# RefOsc10MHz_1V1.net
KiCad netlist of a schematic drawn in EAGLE
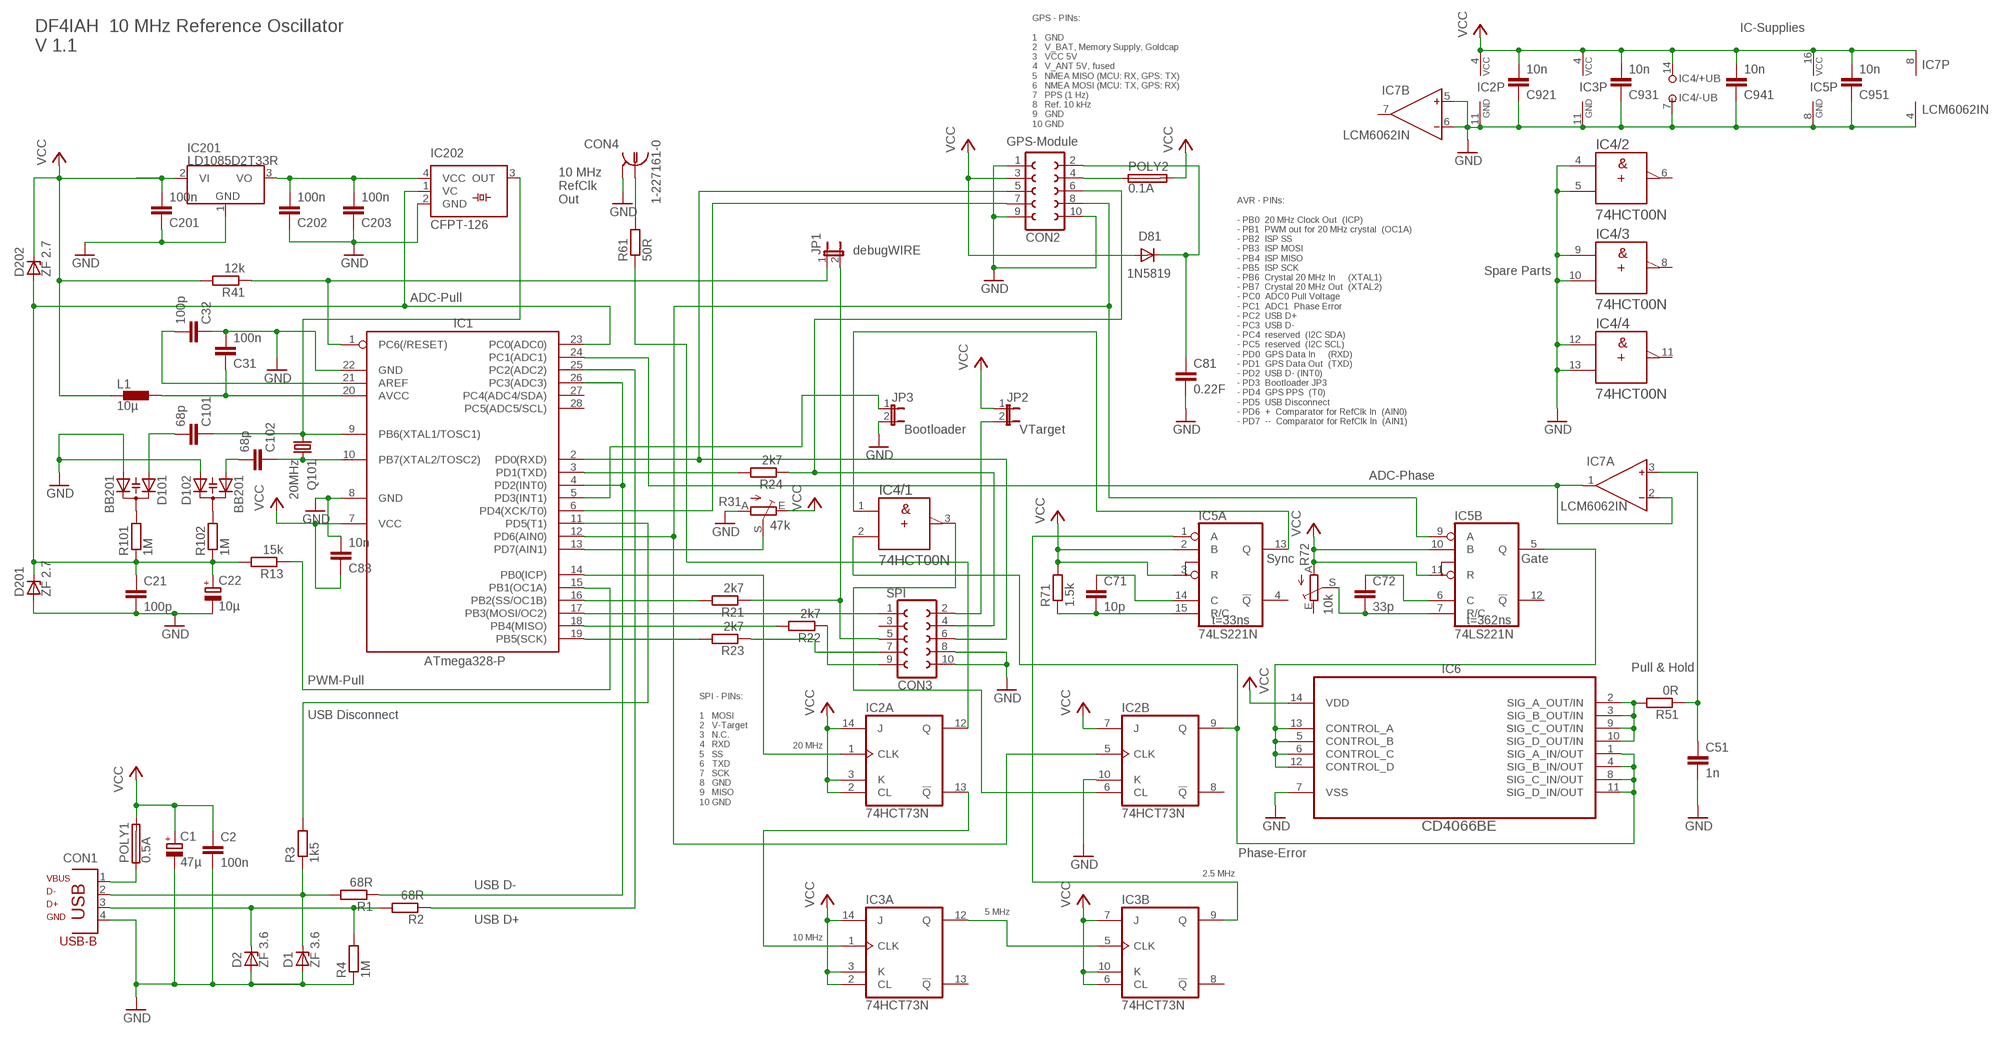
[diagram p0: schematic, sheet 1]

(export (version "E")
  (design (tool "Eeschema 10.0.6"))
  (components
    (comp (ref "C1")
      (value "47µ")
      (footprint "eagle-import:E2-4")
      (libsource (lib "eagle-import") (part "CPOL-EUE2-4"))
    )
    (comp (ref "C2")
      (value "100n")
      (footprint "eagle-import:C5B3")
      (libsource (lib "eagle-import") (part "C5/3"))
    )
    (comp (ref "C21")
      (value "100p")
      (footprint "eagle-import:C5B3")
      (libsource (lib "eagle-import") (part "C5/3"))
    )
    (comp (ref "C22")
      (value "10µ")
      (footprint "eagle-import:E2-4")
      (libsource (lib "eagle-import") (part "CPOL-EUE2-4"))
    )
    (comp (ref "C31")
      (value "100n")
      (footprint "eagle-import:C5B3")
      (libsource (lib "eagle-import") (part "C5/3"))
    )
    (comp (ref "C32")
      (value "100p")
      (footprint "eagle-import:C5B3")
      (libsource (lib "eagle-import") (part "C5/3"))
    )
    (comp (ref "C51")
      (value "1n")
      (footprint "eagle-import:C5B3")
      (libsource (lib "eagle-import") (part "C5/3"))
    )
    (comp (ref "C71")
      (value "10p")
      (footprint "eagle-import:C5B3")
      (libsource (lib "eagle-import") (part "C5/3"))
    )
    (comp (ref "C72")
      (value "33p")
      (footprint "eagle-import:C5B3")
      (libsource (lib "eagle-import") (part "C5/3"))
    )
    (comp (ref "C81")
      (value "0.22F")
      (footprint "eagle-import:C5B7.2")
      (libsource (lib "eagle-import") (part "C5/7.2"))
    )
    (comp (ref "C83")
      (value "10n")
      (footprint "eagle-import:C5B3")
      (libsource (lib "eagle-import") (part "C5/3"))
    )
    (comp (ref "C101")
      (value "68p")
      (footprint "eagle-import:C5B3")
      (libsource (lib "eagle-import") (part "C5/3"))
    )
    (comp (ref "C102")
      (value "68p")
      (footprint "eagle-import:C5B3")
      (libsource (lib "eagle-import") (part "C5/3"))
    )
    (comp (ref "C201")
      (value "100n")
      (footprint "eagle-import:C5B3")
      (libsource (lib "eagle-import") (part "C5/3"))
    )
    (comp (ref "C202")
      (value "100n")
      (footprint "eagle-import:C5B3")
      (libsource (lib "eagle-import") (part "C5/3"))
    )
    (comp (ref "C203")
      (value "100n")
      (footprint "eagle-import:C5B3")
      (libsource (lib "eagle-import") (part "C5/3"))
    )
    (comp (ref "C921")
      (value "10n")
      (footprint "eagle-import:C5B3")
      (libsource (lib "eagle-import") (part "C5/3"))
    )
    (comp (ref "C931")
      (value "10n")
      (footprint "eagle-import:C5B3")
      (libsource (lib "eagle-import") (part "C5/3"))
    )
    (comp (ref "C941")
      (value "10n")
      (footprint "eagle-import:C5B3")
      (libsource (lib "eagle-import") (part "C5/3"))
    )
    (comp (ref "C951")
      (value "10n")
      (footprint "eagle-import:C5B3")
      (libsource (lib "eagle-import") (part "C5/3"))
    )
    (comp (ref "CON1")
      (value "PN61729")
      (footprint "eagle-import:PN61729")
      (libsource (lib "eagle-import") (part "PN61729"))
    )
    (comp (ref "CON2")
      (value "FE05-2")
      (footprint "eagle-import:FE05-2")
      (libsource (lib "eagle-import") (part "FE05-2"))
    )
    (comp (ref "CON3")
      (value "FE05-2")
      (footprint "eagle-import:FE05-2")
      (libsource (lib "eagle-import") (part "FE05-2"))
    )
    (comp (ref "CON4")
      (value "1-227161-0")
      (footprint "eagle-import:AMP_227161")
      (fields (field (name "MF") "TYCO ELECTRONICS") (field (name "MPN") "1-227161"))
      (libsource (lib "eagle-import") (part "?2271611--0"))
    )
    (comp (ref "D1")
      (value "ZF 3.6")
      (footprint "eagle-import:DO41Z10")
      (libsource (lib "eagle-import") (part "1N4728"))
    )
    (comp (ref "D2")
      (value "ZF 3.6")
      (footprint "eagle-import:DO41Z10")
      (libsource (lib "eagle-import") (part "1N4728"))
    )
    (comp (ref "D81")
      (value "1N5819")
      (footprint "eagle-import:DO41-10")
      (libsource (lib "eagle-import") (part "1N4942"))
    )
    (comp (ref "D101")
      (value "BB201")
      (footprint "eagle-import:SOT23")
      (libsource (lib "eagle-import") (part "BBY51"))
    )
    (comp (ref "D102")
      (value "BB201")
      (footprint "eagle-import:SOT23")
      (libsource (lib "eagle-import") (part "BBY51"))
    )
    (comp (ref "D201")
      (value "ZF 2.7")
      (footprint "eagle-import:DO41Z10")
      (libsource (lib "eagle-import") (part "1N4728"))
    )
    (comp (ref "D202")
      (value "ZF 2.7")
      (footprint "eagle-import:DO41Z10")
      (libsource (lib "eagle-import") (part "1N4728"))
    )
    (comp (ref "IC1")
      (value "ATmega328-P")
      (footprint "eagle-import:DIL28-3")
      (libsource (lib "eagle-import") (part "MEGA8-P"))
    )
    (comp (ref "IC2")
      (value "74HCT73N")
      (footprint "eagle-import:DIL14")
      (libsource (lib "eagle-import") (part "7473NLS"))
    )
    (comp (ref "IC3")
      (value "74HCT73N")
      (footprint "eagle-import:DIL14")
      (libsource (lib "eagle-import") (part "7473NLS"))
    )
    (comp (ref "IC4")
      (value "74HCT00N")
      (footprint "eagle-import:DIL14")
      (libsource (lib "eagle-import") (part "7400NHCT"))
    )
    (comp (ref "IC5")
      (value "74LS221N")
      (footprint "eagle-import:DIL16")
      (libsource (lib "eagle-import") (part "74221NLS"))
    )
    (comp (ref "IC6")
      (value "CD4066BE")
      (footprint "eagle-import:DIP254P762X508-14")
      (libsource (lib "eagle-import") (part "CD4066BE"))
    )
    (comp (ref "IC7")
      (value "LCM6062IN")
      (footprint "eagle-import:DIL08")
      (libsource (lib "eagle-import") (part "AD822IN"))
    )
    (comp (ref "IC201")
      (value "LD10853.3")
      (footprint "eagle-import:TO220V")
      (libsource (lib "eagle-import") (part "LD10853.3"))
    )
    (comp (ref "IC202")
      (value "CFPT-126")
      (footprint "eagle-import:SM77H")
      (libsource (lib "eagle-import") (part "CFPT-126"))
    )
    (comp (ref "JP1")
      (value "JP1E")
      (footprint "eagle-import:JP1")
      (libsource (lib "eagle-import") (part "JP1E"))
    )
    (comp (ref "JP2")
      (value "JP1E")
      (footprint "eagle-import:JP1")
      (libsource (lib "eagle-import") (part "JP1E"))
    )
    (comp (ref "JP3")
      (value "JP1E")
      (footprint "eagle-import:JP1")
      (libsource (lib "eagle-import") (part "JP1E"))
    )
    (comp (ref "L1")
      (value "10µ")
      (footprint "eagle-import:BL01RN1A")
      (libsource (lib "eagle-import") (part "BL01RN1A"))
    )
    (comp (ref "POLY1")
      (value "0.5A")
      (footprint "eagle-import:TE5")
      (libsource (lib "eagle-import") (part "FUSETE5"))
    )
    (comp (ref "POLY2")
      (value "0.1A")
      (footprint "eagle-import:TE5")
      (libsource (lib "eagle-import") (part "FUSETE5"))
    )
    (comp (ref "Q101")
      (value "20MHz")
      (footprint "eagle-import:HC49U70")
      (libsource (lib "eagle-import") (part "CRYSTALHC49U70"))
    )
    (comp (ref "R1")
      (value "68R")
      (footprint "eagle-import:0204_7")
      (libsource (lib "eagle-import") (part "R-EU_0204/7"))
    )
    (comp (ref "R2")
      (value "68R")
      (footprint "eagle-import:0204_7")
      (libsource (lib "eagle-import") (part "R-EU_0204/7"))
    )
    (comp (ref "R3")
      (value "1k5")
      (footprint "eagle-import:0204_7")
      (libsource (lib "eagle-import") (part "R-EU_0204/7"))
    )
    (comp (ref "R4")
      (value "1M")
      (footprint "eagle-import:0204_7")
      (libsource (lib "eagle-import") (part "R-EU_0204/7"))
    )
    (comp (ref "R13")
      (value "15k")
      (footprint "eagle-import:0204_7")
      (libsource (lib "eagle-import") (part "R-EU_0204/7"))
    )
    (comp (ref "R21")
      (value "2k7")
      (footprint "eagle-import:0204_7")
      (libsource (lib "eagle-import") (part "R-EU_0204/7"))
    )
    (comp (ref "R22")
      (value "2k7")
      (footprint "eagle-import:0204_7")
      (libsource (lib "eagle-import") (part "R-EU_0204/7"))
    )
    (comp (ref "R23")
      (value "2k7")
      (footprint "eagle-import:0204_7")
      (libsource (lib "eagle-import") (part "R-EU_0204/7"))
    )
    (comp (ref "R24")
      (value "2k7")
      (footprint "eagle-import:0204_7")
      (libsource (lib "eagle-import") (part "R-EU_0204/7"))
    )
    (comp (ref "R31")
      (value "47k")
      (footprint "eagle-import:S64YW")
      (libsource (lib "eagle-import") (part "TRIM_1234-S64YW"))
    )
    (comp (ref "R41")
      (value "12k")
      (footprint "eagle-import:0204_7")
      (libsource (lib "eagle-import") (part "R-EU_0204/7"))
    )
    (comp (ref "R51")
      (value "0R")
      (footprint "eagle-import:0204_7")
      (libsource (lib "eagle-import") (part "R-EU_0204/7"))
    )
    (comp (ref "R61")
      (value "50R")
      (footprint "eagle-import:0204_7")
      (libsource (lib "eagle-import") (part "R-EU_0204/7"))
    )
    (comp (ref "R71")
      (value "1.5k")
      (footprint "eagle-import:0204_7")
      (libsource (lib "eagle-import") (part "R-EU_0204/7"))
    )
    (comp (ref "R72")
      (value "10k")
      (footprint "eagle-import:S64YW")
      (libsource (lib "eagle-import") (part "TRIM_1234-S64YW"))
    )
    (comp (ref "R101")
      (value "1M")
      (footprint "eagle-import:0204_7")
      (libsource (lib "eagle-import") (part "R-EU_0204/7"))
    )
    (comp (ref "R102")
      (value "1M")
      (footprint "eagle-import:0204_7")
      (libsource (lib "eagle-import") (part "R-EU_0204/7"))
    )
  )
  (nets
    (net (code "1") (name "GND") (class "Default")
      (node (ref "C1") (pin "-") (pinfunction "-_-") (pintype "passive"))
      (node (ref "C2") (pin "2") (pinfunction "2_2") (pintype "passive"))
      (node (ref "C201") (pin "1") (pinfunction "1_1") (pintype "passive"))
      (node (ref "C202") (pin "1") (pinfunction "1_1") (pintype "passive"))
      (node (ref "C203") (pin "1") (pinfunction "1_1") (pintype "passive"))
      (node (ref "C21") (pin "2") (pinfunction "2_2") (pintype "passive"))
      (node (ref "C22") (pin "-") (pinfunction "-_-") (pintype "passive"))
      (node (ref "C31") (pin "2") (pinfunction "2_2") (pintype "passive"))
      (node (ref "C32") (pin "1") (pinfunction "1_1") (pintype "passive"))
      (node (ref "C51") (pin "2") (pinfunction "2_2") (pintype "passive"))
      (node (ref "C81") (pin "2") (pinfunction "2_2") (pintype "passive"))
      (node (ref "C83") (pin "2") (pinfunction "2_2") (pintype "passive"))
      (node (ref "C921") (pin "1") (pinfunction "1_1") (pintype "passive"))
      (node (ref "C931") (pin "1") (pinfunction "1_1") (pintype "passive"))
      (node (ref "C941") (pin "1") (pinfunction "1_1") (pintype "passive"))
      (node (ref "C951") (pin "1") (pinfunction "1_1") (pintype "passive"))
      (node (ref "CON1") (pin "4") (pinfunction "4_4") (pintype "passive"))
      (node (ref "CON2") (pin "1") (pinfunction "1_1") (pintype "passive"))
      (node (ref "CON2") (pin "10") (pinfunction "10_10") (pintype "passive"))
      (node (ref "CON2") (pin "9") (pinfunction "9_9") (pintype "passive"))
      (node (ref "CON3") (pin "10") (pinfunction "10_10") (pintype "passive"))
      (node (ref "CON3") (pin "8") (pinfunction "8_8") (pintype "passive"))
      (node (ref "CON4") (pin "2") (pinfunction "2_2") (pintype "passive"))
      (node (ref "D1") (pin "A") (pinfunction "A_A") (pintype "passive"))
      (node (ref "D101") (pin "2") (pinfunction "A2_2") (pintype "passive"))
      (node (ref "D102") (pin "1") (pinfunction "A1_1") (pintype "passive"))
      (node (ref "D2") (pin "A") (pinfunction "A_A") (pintype "passive"))
      (node (ref "D201") (pin "A") (pinfunction "A_A") (pintype "passive"))
      (node (ref "IC1") (pin "22") (pinfunction "GND_22") (pintype "power_in"))
      (node (ref "IC1") (pin "8") (pinfunction "GND_8") (pintype "power_in"))
      (node (ref "IC2") (pin "10") (pinfunction "K_10") (pintype "input"))
      (node (ref "IC2") (pin "11") (pinfunction "GND_11") (pintype "power_in"))
      (node (ref "IC201") (pin "1") (pinfunction "GND_1") (pintype "passive"))
      (node (ref "IC202") (pin "2") (pinfunction "GND_2") (pintype "power_in"))
      (node (ref "IC3") (pin "11") (pinfunction "GND_11") (pintype "power_in"))
      (node (ref "IC4") (pin "10") (pinfunction "B_10") (pintype "input"))
      (node (ref "IC4") (pin "12") (pinfunction "A_12") (pintype "input"))
      (node (ref "IC4") (pin "13") (pinfunction "B_13") (pintype "input"))
      (node (ref "IC4") (pin "4") (pinfunction "A_4") (pintype "input"))
      (node (ref "IC4") (pin "5") (pinfunction "B_5") (pintype "input"))
      (node (ref "IC4") (pin "7") (pinfunction "-UB_7") (pintype "power_in"))
      (node (ref "IC4") (pin "9") (pinfunction "A_9") (pintype "input"))
      (node (ref "IC5") (pin "8") (pinfunction "GND_8") (pintype "power_in"))
      (node (ref "IC6") (pin "7") (pinfunction "VSS_7") (pintype "passive"))
      (node (ref "IC7") (pin "4") (pinfunction "V-_4") (pintype "power_in"))
      (node (ref "IC7") (pin "5") (pinfunction "IN+_5") (pintype "input"))
      (node (ref "IC7") (pin "6") (pinfunction "IN-_6") (pintype "input"))
      (node (ref "JP3") (pin "2") (pinfunction "2_2") (pintype "passive"))
      (node (ref "R31") (pin "A") (pinfunction "A_A") (pintype "passive"))
      (node (ref "R4") (pin "1") (pinfunction "1_1") (pintype "passive"))
    )
    (net (code "2") (name "Net-(C81-Pad1)") (class "Default")
      (node (ref "C81") (pin "1") (pinfunction "1_1") (pintype "passive"))
      (node (ref "CON2") (pin "2") (pinfunction "2_2") (pintype "passive"))
      (node (ref "D81") (pin "C") (pinfunction "C_C") (pintype "passive"))
    )
    (net (code "3") (name "Net-(CON1-Pad1)") (class "Default")
      (node (ref "CON1") (pin "1") (pinfunction "1_1") (pintype "passive"))
      (node (ref "POLY1") (pin "1") (pinfunction "1_1") (pintype "passive"))
    )
    (net (code "4") (name "Net-(CON1-Pad2)") (class "Default")
      (node (ref "CON1") (pin "2") (pinfunction "2_2") (pintype "passive"))
      (node (ref "D1") (pin "C") (pinfunction "C_C") (pintype "passive"))
      (node (ref "R1") (pin "2") (pinfunction "2_2") (pintype "passive"))
      (node (ref "R3") (pin "1") (pinfunction "1_1") (pintype "passive"))
    )
    (net (code "5") (name "Net-(CON1-Pad3)") (class "Default")
      (node (ref "CON1") (pin "3") (pinfunction "3_3") (pintype "passive"))
      (node (ref "D2") (pin "C") (pinfunction "C_C") (pintype "passive"))
      (node (ref "R2") (pin "2") (pinfunction "2_2") (pintype "passive"))
      (node (ref "R4") (pin "2") (pinfunction "2_2") (pintype "passive"))
    )
    (net (code "6") (name "Net-(CON2-Pad4)") (class "Default")
      (node (ref "CON2") (pin "4") (pinfunction "4_4") (pintype "passive"))
      (node (ref "POLY2") (pin "1") (pinfunction "1_1") (pintype "passive"))
    )
    (net (code "7") (name "Net-(CON2-Pad6)") (class "Default")
      (node (ref "CON2") (pin "6") (pinfunction "6_6") (pintype "passive"))
      (node (ref "CON3") (pin "4") (pinfunction "4_4") (pintype "passive"))
      (node (ref "R24") (pin "1") (pinfunction "1_1") (pintype "passive"))
    )
    (net (code "8") (name "Net-(CON3-Pad2)") (class "Default")
      (node (ref "CON3") (pin "2") (pinfunction "2_2") (pintype "passive"))
      (node (ref "JP2") (pin "2") (pinfunction "2_2") (pintype "passive"))
    )
    (net (code "9") (name "Net-(CON3-Pad5)") (class "Default")
      (node (ref "CON3") (pin "5") (pinfunction "5_5") (pintype "passive"))
      (node (ref "JP1") (pin "2") (pinfunction "2_2") (pintype "passive"))
      (node (ref "R21") (pin "1") (pinfunction "1_1") (pintype "passive"))
    )
    (net (code "10") (name "Net-(CON3-Pad7)") (class "Default")
      (node (ref "CON3") (pin "7") (pinfunction "7_7") (pintype "passive"))
      (node (ref "R23") (pin "1") (pinfunction "1_1") (pintype "passive"))
    )
    (net (code "11") (name "Net-(CON3-Pad9)") (class "Default")
      (node (ref "CON3") (pin "9") (pinfunction "9_9") (pintype "passive"))
      (node (ref "R22") (pin "1") (pinfunction "1_1") (pintype "passive"))
    )
    (net (code "12") (name "Net-(CON4-Pad1)") (class "Default")
      (node (ref "CON4") (pin "1") (pinfunction "1_1") (pintype "passive"))
      (node (ref "R61") (pin "2") (pinfunction "2_2") (pintype "passive"))
    )
    (net (code "13") (name "Net-(D101-A1)") (class "Default")
      (node (ref "C101") (pin "2") (pinfunction "2_2") (pintype "passive"))
      (node (ref "D101") (pin "1") (pinfunction "A1_1") (pintype "passive"))
    )
    (net (code "14") (name "Net-(D101-C)") (class "Default")
      (node (ref "D101") (pin "3") (pinfunction "C_3") (pintype "passive"))
      (node (ref "R101") (pin "2") (pinfunction "2_2") (pintype "passive"))
    )
    (net (code "15") (name "Net-(D102-A2)") (class "Default")
      (node (ref "C102") (pin "2") (pinfunction "2_2") (pintype "passive"))
      (node (ref "D102") (pin "2") (pinfunction "A2_2") (pintype "passive"))
    )
    (net (code "16") (name "Net-(D102-C)") (class "Default")
      (node (ref "D102") (pin "3") (pinfunction "C_3") (pintype "passive"))
      (node (ref "R102") (pin "2") (pinfunction "2_2") (pintype "passive"))
    )
    (net (code "17") (name "Net-(IC1-AREF)") (class "Default")
      (node (ref "C32") (pin "2") (pinfunction "2_2") (pintype "passive"))
      (node (ref "IC1") (pin "21") (pinfunction "AREF_21") (pintype "passive"))
    )
    (net (code "18") (name "Net-(IC1-AVCC)") (class "Default")
      (node (ref "C31") (pin "1") (pinfunction "1_1") (pintype "passive"))
      (node (ref "IC1") (pin "20") (pinfunction "AVCC_20") (pintype "power_in"))
      (node (ref "L1") (pin "2") (pinfunction "2_2") (pintype "passive"))
    )
    (net (code "19") (name "Net-(IC1-PB0(ICP))") (class "Default")
      (node (ref "IC1") (pin "14") (pinfunction "PB0(ICP)_14") (pintype "bidirectional"))
      (node (ref "IC2") (pin "1") (pinfunction "CLK_1") (pintype "input"))
    )
    (net (code "20") (name "Net-(IC1-PB1(OC1A))") (class "Default")
      (node (ref "IC1") (pin "15") (pinfunction "PB1(OC1A)_15") (pintype "bidirectional"))
      (node (ref "R13") (pin "1") (pinfunction "1_1") (pintype "passive"))
    )
    (net (code "21") (name "Net-(IC1-PB2(SS{slash}OC1B))") (class "Default")
      (node (ref "IC1") (pin "16") (pinfunction "PB2(SS/OC1B)_16") (pintype "bidirectional"))
      (node (ref "R21") (pin "2") (pinfunction "2_2") (pintype "passive"))
    )
    (net (code "22") (name "Net-(IC1-PB3(MOSI{slash}OC2))") (class "Default")
      (node (ref "CON3") (pin "1") (pinfunction "1_1") (pintype "passive"))
      (node (ref "IC1") (pin "17") (pinfunction "PB3(MOSI/OC2)_17") (pintype "bidirectional"))
    )
    (net (code "23") (name "Net-(IC1-PB4(MISO))") (class "Default")
      (node (ref "IC1") (pin "18") (pinfunction "PB4(MISO)_18") (pintype "bidirectional"))
      (node (ref "R22") (pin "2") (pinfunction "2_2") (pintype "passive"))
    )
    (net (code "24") (name "Net-(IC1-PB5(SCK))") (class "Default")
      (node (ref "IC1") (pin "19") (pinfunction "PB5(SCK)_19") (pintype "bidirectional"))
      (node (ref "R23") (pin "2") (pinfunction "2_2") (pintype "passive"))
    )
    (net (code "25") (name "Net-(IC1-PB6(XTAL1{slash}TOSC1))") (class "Default")
      (node (ref "C101") (pin "1") (pinfunction "1_1") (pintype "passive"))
      (node (ref "IC1") (pin "9") (pinfunction "PB6(XTAL1/TOSC1)_9") (pintype "bidirectional"))
      (node (ref "IC202") (pin "3") (pinfunction "OUT_3") (pintype "output"))
      (node (ref "Q101") (pin "1") (pinfunction "1_1") (pintype "passive"))
    )
    (net (code "26") (name "Net-(IC1-PB7(XTAL2{slash}TOSC2))") (class "Default")
      (node (ref "C102") (pin "1") (pinfunction "1_1") (pintype "passive"))
      (node (ref "IC1") (pin "10") (pinfunction "PB7(XTAL2/TOSC2)_10") (pintype "bidirectional"))
      (node (ref "Q101") (pin "2") (pinfunction "2_2") (pintype "passive"))
    )
    (net (code "27") (name "Net-(IC1-PC0(ADC0))") (class "Default")
      (node (ref "C21") (pin "1") (pinfunction "1_1") (pintype "passive"))
      (node (ref "C22") (pin "+") (pinfunction "+_+") (pintype "passive"))
      (node (ref "D201") (pin "C") (pinfunction "C_C") (pintype "passive"))
      (node (ref "D202") (pin "A") (pinfunction "A_A") (pintype "passive"))
      (node (ref "IC1") (pin "23") (pinfunction "PC0(ADC0)_23") (pintype "bidirectional"))
      (node (ref "IC202") (pin "1") (pinfunction "VC_1") (pintype "input"))
      (node (ref "R101") (pin "1") (pinfunction "1_1") (pintype "passive"))
      (node (ref "R102") (pin "1") (pinfunction "1_1") (pintype "passive"))
      (node (ref "R13") (pin "2") (pinfunction "2_2") (pintype "passive"))
    )
    (net (code "28") (name "Net-(IC1-PC1(ADC1))") (class "Default")
      (node (ref "IC1") (pin "24") (pinfunction "PC1(ADC1)_24") (pintype "bidirectional"))
      (node (ref "IC7") (pin "1") (pinfunction "OUT_1") (pintype "output"))
      (node (ref "IC7") (pin "2") (pinfunction "IN-_2") (pintype "input"))
    )
    (net (code "29") (name "Net-(IC1-PC2(ADC2))") (class "Default")
      (node (ref "IC1") (pin "25") (pinfunction "PC2(ADC2)_25") (pintype "bidirectional"))
      (node (ref "R2") (pin "1") (pinfunction "1_1") (pintype "passive"))
    )
    (net (code "30") (name "Net-(IC1-PC3(ADC3))") (class "Default")
      (node (ref "IC1") (pin "26") (pinfunction "PC3(ADC3)_26") (pintype "bidirectional"))
      (node (ref "IC1") (pin "4") (pinfunction "PD2(INT0)_4") (pintype "bidirectional"))
      (node (ref "R1") (pin "1") (pinfunction "1_1") (pintype "passive"))
    )
    (net (code "31") (name "Net-(IC1-PC6({slash}RESET))") (class "Default")
      (node (ref "IC1") (pin "1") (pinfunction "PC6(/RESET)_1") (pintype "bidirectional"))
      (node (ref "JP1") (pin "1") (pinfunction "1_1") (pintype "passive"))
      (node (ref "R41") (pin "1") (pinfunction "1_1") (pintype "passive"))
    )
    (net (code "32") (name "Net-(IC1-PD0(RXD))") (class "Default")
      (node (ref "CON2") (pin "5") (pinfunction "5_5") (pintype "passive"))
      (node (ref "CON3") (pin "6") (pinfunction "6_6") (pintype "passive"))
      (node (ref "IC1") (pin "2") (pinfunction "PD0(RXD)_2") (pintype "bidirectional"))
    )
    (net (code "33") (name "Net-(IC1-PD1(TXD))") (class "Default")
      (node (ref "IC1") (pin "3") (pinfunction "PD1(TXD)_3") (pintype "bidirectional"))
      (node (ref "R24") (pin "2") (pinfunction "2_2") (pintype "passive"))
    )
    (net (code "34") (name "Net-(IC1-PD3(INT1))") (class "Default")
      (node (ref "IC1") (pin "5") (pinfunction "PD3(INT1)_5") (pintype "bidirectional"))
      (node (ref "JP3") (pin "1") (pinfunction "1_1") (pintype "passive"))
    )
    (net (code "35") (name "Net-(IC1-PD4(XCK{slash}T0))") (class "Default")
      (node (ref "CON2") (pin "7") (pinfunction "7_7") (pintype "passive"))
      (node (ref "IC1") (pin "6") (pinfunction "PD4(XCK/T0)_6") (pintype "bidirectional"))
    )
    (net (code "36") (name "Net-(IC1-PD5(T1))") (class "Default")
      (node (ref "IC1") (pin "11") (pinfunction "PD5(T1)_11") (pintype "bidirectional"))
      (node (ref "R3") (pin "2") (pinfunction "2_2") (pintype "passive"))
    )
    (net (code "37") (name "Net-(IC1-PD6(AIN0))") (class "Default")
      (node (ref "CON2") (pin "8") (pinfunction "8_8") (pintype "passive"))
      (node (ref "IC1") (pin "12") (pinfunction "PD6(AIN0)_12") (pintype "bidirectional"))
      (node (ref "IC2") (pin "5") (pinfunction "CLK_5") (pintype "input"))
      (node (ref "IC5") (pin "9") (pinfunction "A_9") (pintype "input"))
    )
    (net (code "38") (name "Net-(IC1-PD7(AIN1))") (class "Default")
      (node (ref "IC1") (pin "13") (pinfunction "PD7(AIN1)_13") (pintype "bidirectional"))
      (node (ref "R31") (pin "S") (pinfunction "S_S") (pintype "passive"))
    )
    (net (code "39") (name "Net-(IC2A-Q)") (class "Default")
      (node (ref "IC2") (pin "12") (pinfunction "Q_12") (pintype "output"))
      (node (ref "R61") (pin "1") (pinfunction "1_1") (pintype "passive"))
    )
    (net (code "40") (name "Net-(IC2A-~{Q})") (class "Default")
      (node (ref "IC2") (pin "13") (pinfunction "~{Q}_13") (pintype "output"))
      (node (ref "IC3") (pin "1") (pinfunction "CLK_1") (pintype "input"))
    )
    (net (code "41") (name "Net-(IC2B-CL)") (class "Default")
      (node (ref "IC2") (pin "6") (pinfunction "CL_6") (pintype "input"))
      (node (ref "IC4") (pin "3") (pinfunction "Y_3") (pintype "output"))
    )
    (net (code "42") (name "Net-(IC2B-Q)") (class "Default")
      (node (ref "IC2") (pin "9") (pinfunction "Q_9") (pintype "output"))
      (node (ref "IC4") (pin "2") (pinfunction "B_2") (pintype "input"))
      (node (ref "IC6") (pin "1") (pinfunction "SIG_A_IN/OUT_1") (pintype "bidirectional"))
      (node (ref "IC6") (pin "11") (pinfunction "SIG_D_IN/OUT_11") (pintype "bidirectional"))
      (node (ref "IC6") (pin "4") (pinfunction "SIG_B_IN/OUT_4") (pintype "bidirectional"))
      (node (ref "IC6") (pin "8") (pinfunction "SIG_C_IN/OUT_8") (pintype "bidirectional"))
    )
    (net (code "43") (name "Net-(IC3A-Q)") (class "Default")
      (node (ref "IC3") (pin "12") (pinfunction "Q_12") (pintype "output"))
      (node (ref "IC3") (pin "5") (pinfunction "CLK_5") (pintype "input"))
    )
    (net (code "44") (name "Net-(IC3B-Q)") (class "Default")
      (node (ref "IC3") (pin "9") (pinfunction "Q_9") (pintype "output"))
      (node (ref "IC5") (pin "1") (pinfunction "A_1") (pintype "input"))
    )
    (net (code "45") (name "Net-(IC4C-A)") (class "Default")
      (node (ref "IC4") (pin "1") (pinfunction "A_1") (pintype "input"))
      (node (ref "IC5") (pin "13") (pinfunction "Q_13") (pintype "output"))
    )
    (net (code "46") (name "Net-(IC5A-C)") (class "Default")
      (node (ref "C71") (pin "1") (pinfunction "1_1") (pintype "passive"))
      (node (ref "IC5") (pin "14") (pinfunction "C_14") (pintype "input"))
    )
    (net (code "47") (name "Net-(IC5A-R{slash}C)") (class "Default")
      (node (ref "C71") (pin "2") (pinfunction "2_2") (pintype "passive"))
      (node (ref "IC5") (pin "15") (pinfunction "R/C_15") (pintype "input"))
      (node (ref "R71") (pin "1") (pinfunction "1_1") (pintype "passive"))
    )
    (net (code "48") (name "Net-(IC5B-C)") (class "Default")
      (node (ref "C72") (pin "1") (pinfunction "1_1") (pintype "passive"))
      (node (ref "IC5") (pin "6") (pinfunction "C_6") (pintype "input"))
    )
    (net (code "49") (name "Net-(IC5B-Q)") (class "Default")
      (node (ref "IC5") (pin "5") (pinfunction "Q_5") (pintype "output"))
      (node (ref "IC6") (pin "12") (pinfunction "CONTROL_D_12") (pintype "input"))
      (node (ref "IC6") (pin "13") (pinfunction "CONTROL_A_13") (pintype "input"))
      (node (ref "IC6") (pin "5") (pinfunction "CONTROL_B_5") (pintype "input"))
      (node (ref "IC6") (pin "6") (pinfunction "CONTROL_C_6") (pintype "input"))
    )
    (net (code "50") (name "Net-(IC5B-R{slash}C)") (class "Default")
      (node (ref "C72") (pin "2") (pinfunction "2_2") (pintype "passive"))
      (node (ref "IC5") (pin "7") (pinfunction "R/C_7") (pintype "input"))
      (node (ref "R72") (pin "S") (pinfunction "S_S") (pintype "passive"))
    )
    (net (code "51") (name "Net-(IC6-SIG_A_OUT{slash}IN)") (class "Default")
      (node (ref "IC6") (pin "10") (pinfunction "SIG_D_OUT/IN_10") (pintype "bidirectional"))
      (node (ref "IC6") (pin "2") (pinfunction "SIG_A_OUT/IN_2") (pintype "bidirectional"))
      (node (ref "IC6") (pin "3") (pinfunction "SIG_B_OUT/IN_3") (pintype "bidirectional"))
      (node (ref "IC6") (pin "9") (pinfunction "SIG_C_OUT/IN_9") (pintype "bidirectional"))
      (node (ref "R51") (pin "2") (pinfunction "2_2") (pintype "passive"))
    )
    (net (code "52") (name "Net-(IC7A-IN+)") (class "Default")
      (node (ref "C51") (pin "1") (pinfunction "1_1") (pintype "passive"))
      (node (ref "IC7") (pin "3") (pinfunction "IN+_3") (pintype "input"))
      (node (ref "R51") (pin "1") (pinfunction "1_1") (pintype "passive"))
    )
    (net (code "53") (name "Net-(IC201-VO)") (class "Default")
      (node (ref "C202") (pin "2") (pinfunction "2_2") (pintype "passive"))
      (node (ref "C203") (pin "2") (pinfunction "2_2") (pintype "passive"))
      (node (ref "IC201") (pin "3") (pinfunction "VO_3") (pintype "passive"))
      (node (ref "IC202") (pin "4") (pinfunction "VCC_4") (pintype "power_in"))
    )
    (net (code "54") (name "VCC") (class "Default")
      (node (ref "C1") (pin "+") (pinfunction "+_+") (pintype "passive"))
      (node (ref "C2") (pin "1") (pinfunction "1_1") (pintype "passive"))
      (node (ref "C201") (pin "2") (pinfunction "2_2") (pintype "passive"))
      (node (ref "C83") (pin "1") (pinfunction "1_1") (pintype "passive"))
      (node (ref "C921") (pin "2") (pinfunction "2_2") (pintype "passive"))
      (node (ref "C931") (pin "2") (pinfunction "2_2") (pintype "passive"))
      (node (ref "C941") (pin "2") (pinfunction "2_2") (pintype "passive"))
      (node (ref "C951") (pin "2") (pinfunction "2_2") (pintype "passive"))
      (node (ref "CON2") (pin "3") (pinfunction "3_3") (pintype "passive"))
      (node (ref "D202") (pin "C") (pinfunction "C_C") (pintype "passive"))
      (node (ref "D81") (pin "A") (pinfunction "A_A") (pintype "passive"))
      (node (ref "IC1") (pin "7") (pinfunction "VCC_7") (pintype "power_in"))
      (node (ref "IC2") (pin "14") (pinfunction "J_14") (pintype "input"))
      (node (ref "IC2") (pin "2") (pinfunction "CL_2") (pintype "input"))
      (node (ref "IC2") (pin "3") (pinfunction "K_3") (pintype "input"))
      (node (ref "IC2") (pin "4") (pinfunction "VCC_4") (pintype "power_in"))
      (node (ref "IC2") (pin "7") (pinfunction "J_7") (pintype "input"))
      (node (ref "IC201") (pin "2") (pinfunction "VI_2") (pintype "input"))
      (node (ref "IC3") (pin "10") (pinfunction "K_10") (pintype "input"))
      (node (ref "IC3") (pin "14") (pinfunction "J_14") (pintype "input"))
      (node (ref "IC3") (pin "2") (pinfunction "CL_2") (pintype "input"))
      (node (ref "IC3") (pin "3") (pinfunction "K_3") (pintype "input"))
      (node (ref "IC3") (pin "4") (pinfunction "VCC_4") (pintype "power_in"))
      (node (ref "IC3") (pin "6") (pinfunction "CL_6") (pintype "input"))
      (node (ref "IC3") (pin "7") (pinfunction "J_7") (pintype "input"))
      (node (ref "IC4") (pin "14") (pinfunction "+UB_14") (pintype "power_in"))
      (node (ref "IC5") (pin "10") (pinfunction "B_10") (pintype "input"))
      (node (ref "IC5") (pin "11") (pinfunction "R_11") (pintype "input"))
      (node (ref "IC5") (pin "16") (pinfunction "VCC_16") (pintype "power_in"))
      (node (ref "IC5") (pin "2") (pinfunction "B_2") (pintype "input"))
      (node (ref "IC5") (pin "3") (pinfunction "R_3") (pintype "input"))
      (node (ref "IC6") (pin "14") (pinfunction "VDD_14") (pintype "power_in"))
      (node (ref "IC7") (pin "8") (pinfunction "V+_8") (pintype "power_in"))
      (node (ref "JP2") (pin "1") (pinfunction "1_1") (pintype "passive"))
      (node (ref "L1") (pin "1") (pinfunction "1_1") (pintype "passive"))
      (node (ref "POLY1") (pin "2") (pinfunction "2_2") (pintype "passive"))
      (node (ref "POLY2") (pin "2") (pinfunction "2_2") (pintype "passive"))
      (node (ref "R31") (pin "E") (pinfunction "E_E") (pintype "passive"))
      (node (ref "R41") (pin "2") (pinfunction "2_2") (pintype "passive"))
      (node (ref "R71") (pin "2") (pinfunction "2_2") (pintype "passive"))
      (node (ref "R72") (pin "A") (pinfunction "A_A") (pintype "passive"))
    )
    (net (code "55") (name "unconnected-(CON3-Pad3)") (class "Default")
      (node (ref "CON3") (pin "3") (pinfunction "3_3") (pintype "passive"))
    )
    (net (code "56") (name "unconnected-(IC1-PC4(ADC4{slash}SDA)-Pad27)") (class "Default")
      (node (ref "IC1") (pin "27") (pinfunction "PC4(ADC4/SDA)_27") (pintype "bidirectional"))
    )
    (net (code "57") (name "unconnected-(IC1-PC5(ADC5{slash}SCL)-Pad28)") (class "Default")
      (node (ref "IC1") (pin "28") (pinfunction "PC5(ADC5/SCL)_28") (pintype "bidirectional"))
    )
    (net (code "58") (name "unconnected-(IC2B-~{Q}-Pad8)") (class "Default")
      (node (ref "IC2") (pin "8") (pinfunction "~{Q}_8") (pintype "output"))
    )
    (net (code "59") (name "unconnected-(IC3A-~{Q}-Pad13)") (class "Default")
      (node (ref "IC3") (pin "13") (pinfunction "~{Q}_13") (pintype "output"))
    )
    (net (code "60") (name "unconnected-(IC3B-~{Q}-Pad8)") (class "Default")
      (node (ref "IC3") (pin "8") (pinfunction "~{Q}_8") (pintype "output"))
    )
    (net (code "61") (name "unconnected-(IC4D-Y-Pad6)") (class "Default")
      (node (ref "IC4") (pin "6") (pinfunction "Y_6") (pintype "output"))
    )
    (net (code "62") (name "unconnected-(IC4E-Y-Pad8)") (class "Default")
      (node (ref "IC4") (pin "8") (pinfunction "Y_8") (pintype "output"))
    )
    (net (code "63") (name "unconnected-(IC4F-Y-Pad11)") (class "Default")
      (node (ref "IC4") (pin "11") (pinfunction "Y_11") (pintype "output"))
    )
    (net (code "64") (name "unconnected-(IC5A-~{Q}-Pad4)") (class "Default")
      (node (ref "IC5") (pin "4") (pinfunction "~{Q}_4") (pintype "output"))
    )
    (net (code "65") (name "unconnected-(IC5B-~{Q}-Pad12)") (class "Default")
      (node (ref "IC5") (pin "12") (pinfunction "~{Q}_12") (pintype "output"))
    )
    (net (code "66") (name "unconnected-(IC7B-OUT-Pad7)") (class "Default")
      (node (ref "IC7") (pin "7") (pinfunction "OUT_7") (pintype "output"))
    )
    (net (code "67") (name "unconnected-(R31-S-PadS@1)") (class "Default")
      (node (ref "R31") (pin "S@1") (pinfunction "S_S@1") (pintype "passive"))
    )
    (net (code "68") (name "unconnected-(R72-PadE)") (class "Default")
      (node (ref "R72") (pin "E") (pinfunction "E_E") (pintype "passive"))
    )
    (net (code "69") (name "unconnected-(R72-S-PadS@1)") (class "Default")
      (node (ref "R72") (pin "S@1") (pinfunction "S_S@1") (pintype "passive"))
    )
  )
)
